# RK3566_SARADC_GPIO.net
KiCad netlist of a schematic drawn in Altium Designer
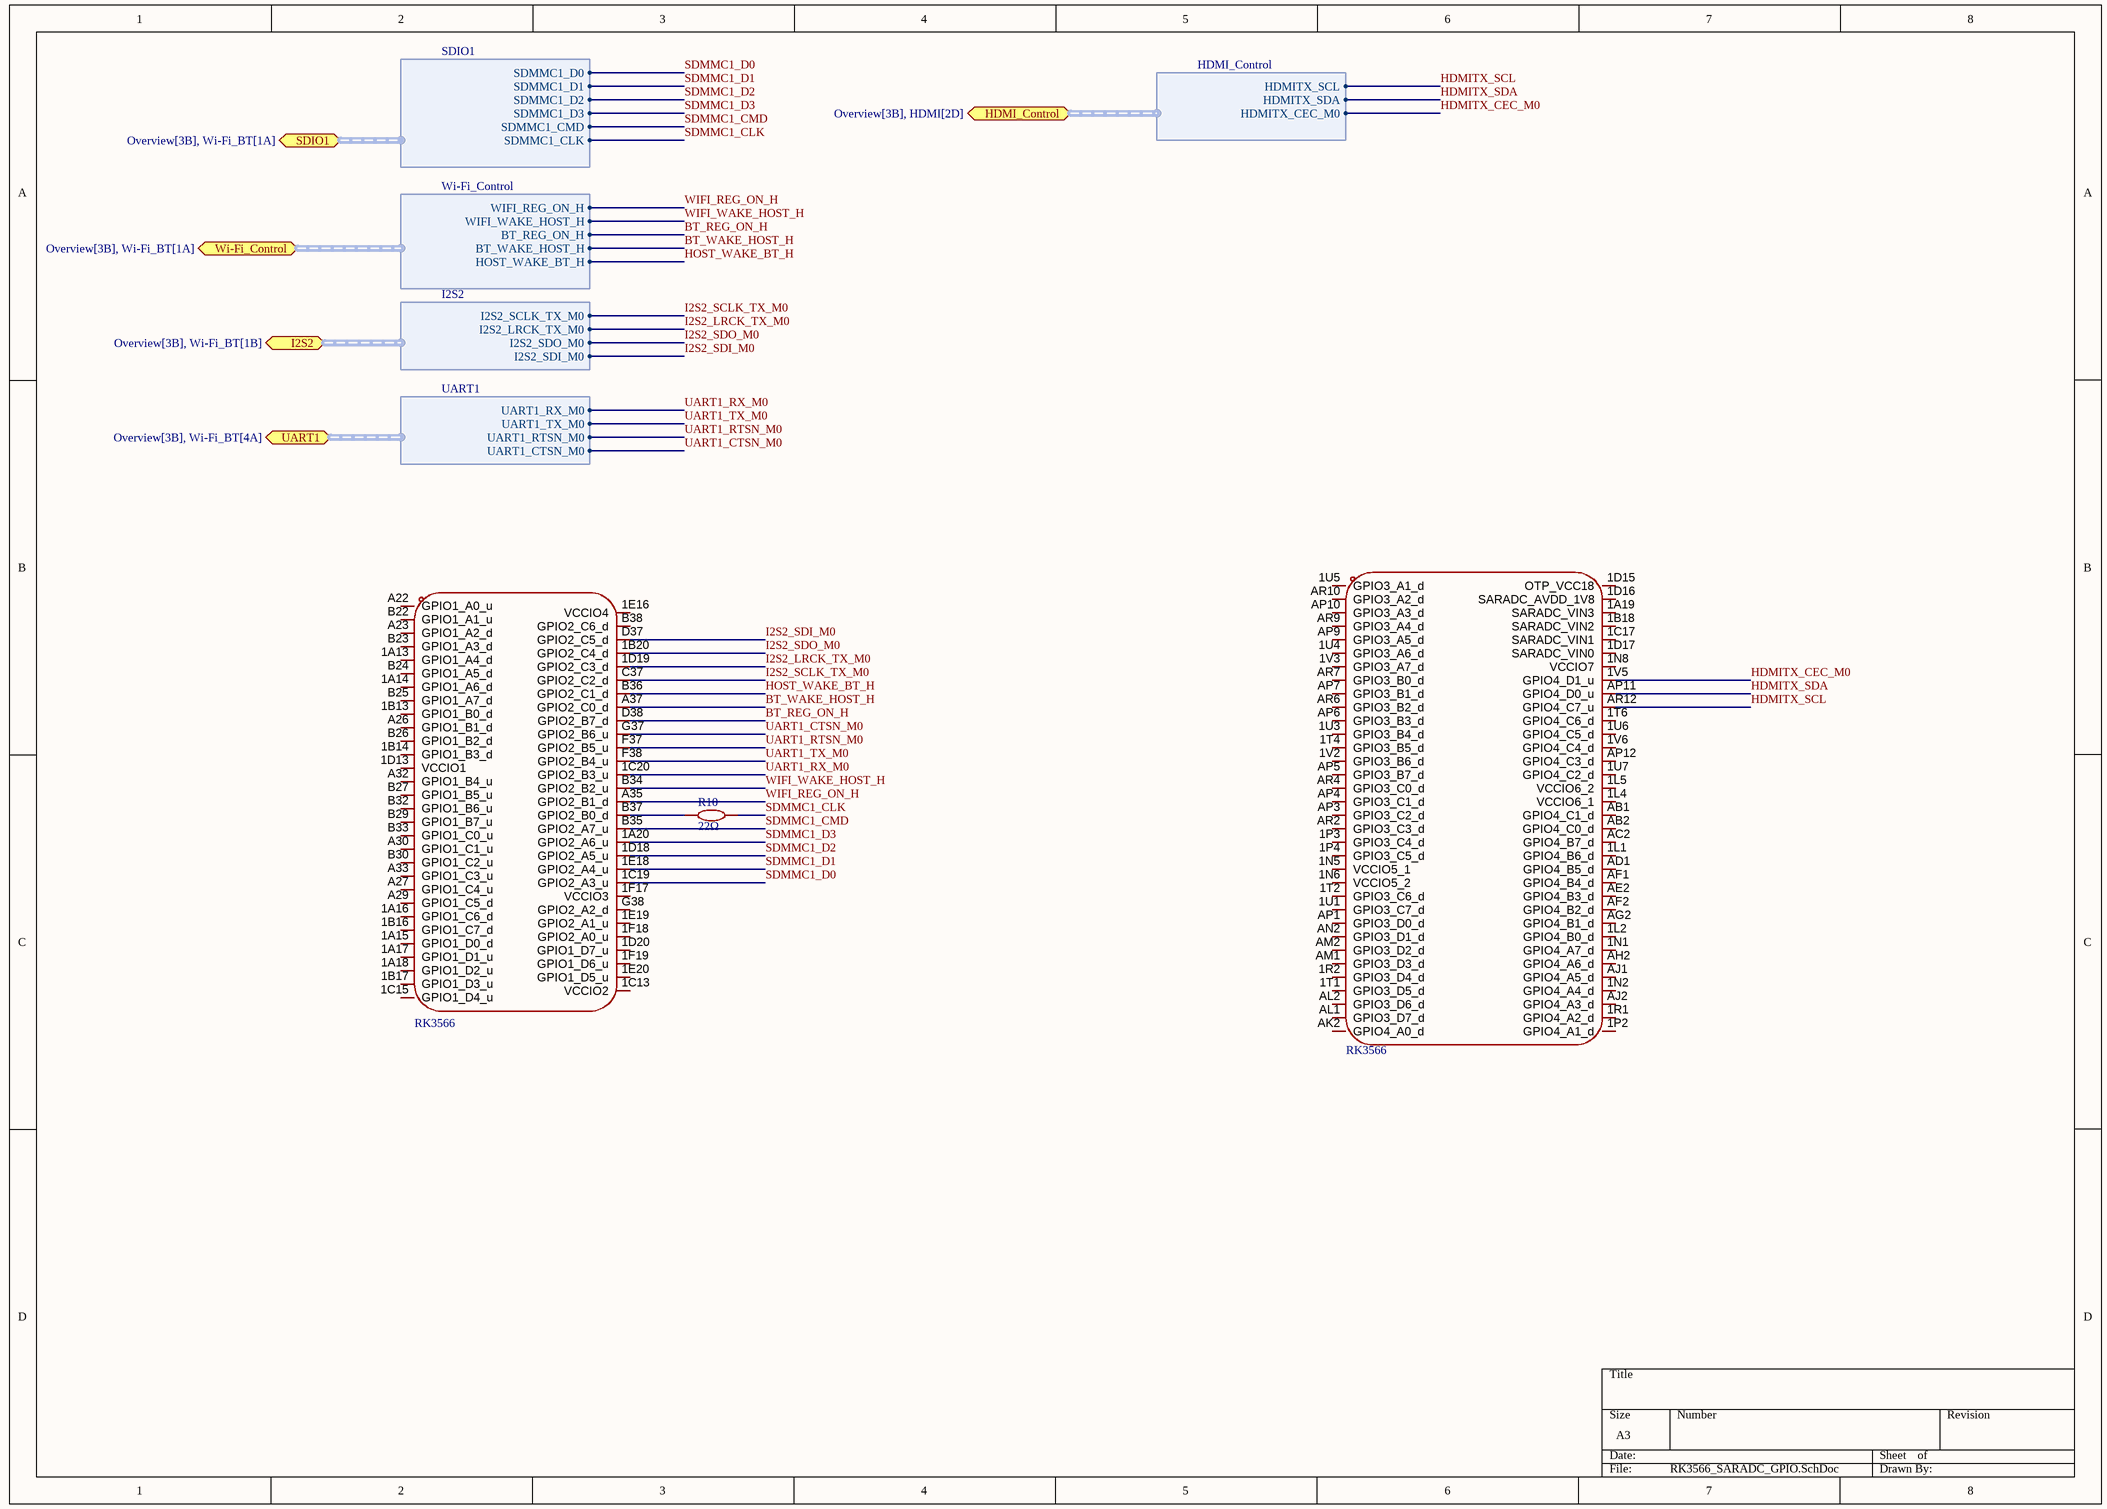
[diagram p0: RK3566_SARADC_GPIO.SchDoc]

(export (version "E")
  (design (tool "Eeschema 10.0.6"))
  (components
    (comp (ref "R10")
      (value "22Ω")
      (footprint "R0402")
      (description "62.5mW 33Ω 50V ±100ppm/℃ Thick Film Resistor ±1% 0402 Chip Resistor - Surface Mount ROHS")
      (libsource (lib "RLC") (part "22Ω"))
    )
    (comp (ref "U1")
      (value "RK3566")
      (footprint "BGA-565_L15.5-W14.4-P0.40_RK3566_1")
      (description "BGA-565(15.5x14.4)")
      (libsource (lib "IC") (part "RK3566"))
    )
  )
  (nets
    (net (code "6") (name "/BT_REG_ON_H") (class "Default")
      (node (ref "U1") (pin "D38") (pinfunction "GPIO2_B7_d_D38") (pintype "passive"))
    )
    (net (code "7") (name "/BT_WAKE_HOST_H") (class "Default")
      (node (ref "U1") (pin "A37") (pinfunction "GPIO2_C0_d_A37") (pintype "passive"))
    )
    (net (code "8") (name "/HDMITX_CEC_M0") (class "Default")
      (node (ref "U1") (pin "1V5") (pinfunction "GPIO4_D1_u_1V5") (pintype "passive"))
    )
    (net (code "9") (name "/HDMITX_SCL") (class "Default")
      (node (ref "U1") (pin "AR12") (pinfunction "GPIO4_C7_u_AR12") (pintype "passive"))
    )
    (net (code "10") (name "/HDMITX_SDA") (class "Default")
      (node (ref "U1") (pin "AP11") (pinfunction "GPIO4_D0_u_AP11") (pintype "passive"))
    )
    (net (code "11") (name "/HOST_WAKE_BT_H") (class "Default")
      (node (ref "U1") (pin "B36") (pinfunction "GPIO2_C1_d_B36") (pintype "passive"))
    )
    (net (code "12") (name "/I2S2_LRCK_TX_M0") (class "Default")
      (node (ref "U1") (pin "1D19") (pinfunction "GPIO2_C3_d_1D19") (pintype "passive"))
    )
    (net (code "13") (name "/I2S2_SCLK_TX_M0") (class "Default")
      (node (ref "U1") (pin "C37") (pinfunction "GPIO2_C2_d_C37") (pintype "passive"))
    )
    (net (code "14") (name "/I2S2_SDI_M0") (class "Default")
      (node (ref "U1") (pin "D37") (pinfunction "GPIO2_C5_d_D37") (pintype "passive"))
    )
    (net (code "15") (name "/I2S2_SDO_M0") (class "Default")
      (node (ref "U1") (pin "1B20") (pinfunction "GPIO2_C4_d_1B20") (pintype "passive"))
    )
    (net (code "16") (name "/SDMMC1_CLK") (class "Default")
      (node (ref "R10") (pin "2") (pinfunction "2_2") (pintype "passive"))
    )
    (net (code "17") (name "/SDMMC1_CMD") (class "Default")
      (node (ref "U1") (pin "B35") (pinfunction "GPIO2_A7_u_B35") (pintype "passive"))
    )
    (net (code "18") (name "/SDMMC1_D0") (class "Default")
      (node (ref "U1") (pin "1C19") (pinfunction "GPIO2_A3_u_1C19") (pintype "passive"))
    )
    (net (code "19") (name "/SDMMC1_D1") (class "Default")
      (node (ref "U1") (pin "1E18") (pinfunction "GPIO2_A4_u_1E18") (pintype "passive"))
    )
    (net (code "20") (name "/SDMMC1_D2") (class "Default")
      (node (ref "U1") (pin "1D18") (pinfunction "GPIO2_A5_u_1D18") (pintype "passive"))
    )
    (net (code "21") (name "/SDMMC1_D3") (class "Default")
      (node (ref "U1") (pin "1A20") (pinfunction "GPIO2_A6_u_1A20") (pintype "passive"))
    )
    (net (code "22") (name "/UART1_CTSN_M0") (class "Default")
      (node (ref "U1") (pin "G37") (pinfunction "GPIO2_B6_u_G37") (pintype "passive"))
    )
    (net (code "23") (name "/UART1_RTSN_M0") (class "Default")
      (node (ref "U1") (pin "F37") (pinfunction "GPIO2_B5_u_F37") (pintype "passive"))
    )
    (net (code "24") (name "/UART1_RX_M0") (class "Default")
      (node (ref "U1") (pin "1C20") (pinfunction "GPIO2_B3_u_1C20") (pintype "passive"))
    )
    (net (code "25") (name "/UART1_TX_M0") (class "Default")
      (node (ref "U1") (pin "F38") (pinfunction "GPIO2_B4_u_F38") (pintype "passive"))
    )
    (net (code "26") (name "/WIFI_REG_ON_H") (class "Default")
      (node (ref "U1") (pin "A35") (pinfunction "GPIO2_B1_d_A35") (pintype "passive"))
    )
    (net (code "27") (name "/WIFI_WAKE_HOST_H") (class "Default")
      (node (ref "U1") (pin "B34") (pinfunction "GPIO2_B2_u_B34") (pintype "passive"))
    )
    (net (code "33") (name "Net-(U1E-GPIO2_B0_d)") (class "Default")
      (node (ref "R10") (pin "1") (pinfunction "1_1") (pintype "passive"))
      (node (ref "U1") (pin "B37") (pinfunction "GPIO2_B0_d_B37") (pintype "passive"))
    )
    (net (code "34") (name "unconnected-(U1E-GPIO1_A0_u-PadA22)") (class "Default")
      (node (ref "U1") (pin "A22") (pinfunction "GPIO1_A0_u_A22") (pintype "passive"))
    )
    (net (code "35") (name "unconnected-(U1E-GPIO1_A1_u-PadB22)") (class "Default")
      (node (ref "U1") (pin "B22") (pinfunction "GPIO1_A1_u_B22") (pintype "passive"))
    )
    (net (code "36") (name "unconnected-(U1E-GPIO1_A2_d-PadA23)") (class "Default")
      (node (ref "U1") (pin "A23") (pinfunction "GPIO1_A2_d_A23") (pintype "passive"))
    )
    (net (code "37") (name "unconnected-(U1E-GPIO1_A3_d-PadB23)") (class "Default")
      (node (ref "U1") (pin "B23") (pinfunction "GPIO1_A3_d_B23") (pintype "passive"))
    )
    (net (code "38") (name "unconnected-(U1E-GPIO1_A4_d-Pad1A13)") (class "Default")
      (node (ref "U1") (pin "1A13") (pinfunction "GPIO1_A4_d_1A13") (pintype "passive"))
    )
    (net (code "39") (name "unconnected-(U1E-GPIO1_A5_d-PadB24)") (class "Default")
      (node (ref "U1") (pin "B24") (pinfunction "GPIO1_A5_d_B24") (pintype "passive"))
    )
    (net (code "40") (name "unconnected-(U1E-GPIO1_A6_d-Pad1A14)") (class "Default")
      (node (ref "U1") (pin "1A14") (pinfunction "GPIO1_A6_d_1A14") (pintype "passive"))
    )
    (net (code "41") (name "unconnected-(U1E-GPIO1_A7_d-PadB25)") (class "Default")
      (node (ref "U1") (pin "B25") (pinfunction "GPIO1_A7_d_B25") (pintype "passive"))
    )
    (net (code "42") (name "unconnected-(U1E-GPIO1_B0_d-Pad1B13)") (class "Default")
      (node (ref "U1") (pin "1B13") (pinfunction "GPIO1_B0_d_1B13") (pintype "passive"))
    )
    (net (code "43") (name "unconnected-(U1E-GPIO1_B1_d-PadA26)") (class "Default")
      (node (ref "U1") (pin "A26") (pinfunction "GPIO1_B1_d_A26") (pintype "passive"))
    )
    (net (code "44") (name "unconnected-(U1E-GPIO1_B2_d-PadB26)") (class "Default")
      (node (ref "U1") (pin "B26") (pinfunction "GPIO1_B2_d_B26") (pintype "passive"))
    )
    (net (code "45") (name "unconnected-(U1E-GPIO1_B3_d-Pad1B14)") (class "Default")
      (node (ref "U1") (pin "1B14") (pinfunction "GPIO1_B3_d_1B14") (pintype "passive"))
    )
    (net (code "46") (name "unconnected-(U1E-GPIO1_B4_u-PadA32)") (class "Default")
      (node (ref "U1") (pin "A32") (pinfunction "GPIO1_B4_u_A32") (pintype "passive"))
    )
    (net (code "47") (name "unconnected-(U1E-GPIO1_B5_u-PadB27)") (class "Default")
      (node (ref "U1") (pin "B27") (pinfunction "GPIO1_B5_u_B27") (pintype "passive"))
    )
    (net (code "48") (name "unconnected-(U1E-GPIO1_B6_u-PadB32)") (class "Default")
      (node (ref "U1") (pin "B32") (pinfunction "GPIO1_B6_u_B32") (pintype "passive"))
    )
    (net (code "49") (name "unconnected-(U1E-GPIO1_B7_u-PadB29)") (class "Default")
      (node (ref "U1") (pin "B29") (pinfunction "GPIO1_B7_u_B29") (pintype "passive"))
    )
    (net (code "50") (name "unconnected-(U1E-GPIO1_C0_u-PadB33)") (class "Default")
      (node (ref "U1") (pin "B33") (pinfunction "GPIO1_C0_u_B33") (pintype "passive"))
    )
    (net (code "51") (name "unconnected-(U1E-GPIO1_C1_u-PadA30)") (class "Default")
      (node (ref "U1") (pin "A30") (pinfunction "GPIO1_C1_u_A30") (pintype "passive"))
    )
    (net (code "52") (name "unconnected-(U1E-GPIO1_C2_u-PadB30)") (class "Default")
      (node (ref "U1") (pin "B30") (pinfunction "GPIO1_C2_u_B30") (pintype "passive"))
    )
    (net (code "53") (name "unconnected-(U1E-GPIO1_C3_u-PadA33)") (class "Default")
      (node (ref "U1") (pin "A33") (pinfunction "GPIO1_C3_u_A33") (pintype "passive"))
    )
    (net (code "54") (name "unconnected-(U1E-GPIO1_C4_u-PadA27)") (class "Default")
      (node (ref "U1") (pin "A27") (pinfunction "GPIO1_C4_u_A27") (pintype "passive"))
    )
    (net (code "55") (name "unconnected-(U1E-GPIO1_C5_d-PadA29)") (class "Default")
      (node (ref "U1") (pin "A29") (pinfunction "GPIO1_C5_d_A29") (pintype "passive"))
    )
    (net (code "56") (name "unconnected-(U1E-GPIO1_C6_d-Pad1A16)") (class "Default")
      (node (ref "U1") (pin "1A16") (pinfunction "GPIO1_C6_d_1A16") (pintype "passive"))
    )
    (net (code "57") (name "unconnected-(U1E-GPIO1_C7_d-Pad1B16)") (class "Default")
      (node (ref "U1") (pin "1B16") (pinfunction "GPIO1_C7_d_1B16") (pintype "passive"))
    )
    (net (code "58") (name "unconnected-(U1E-GPIO1_D0_d-Pad1A15)") (class "Default")
      (node (ref "U1") (pin "1A15") (pinfunction "GPIO1_D0_d_1A15") (pintype "passive"))
    )
    (net (code "59") (name "unconnected-(U1E-GPIO1_D1_u-Pad1A17)") (class "Default")
      (node (ref "U1") (pin "1A17") (pinfunction "GPIO1_D1_u_1A17") (pintype "passive"))
    )
    (net (code "60") (name "unconnected-(U1E-GPIO1_D2_u-Pad1A18)") (class "Default")
      (node (ref "U1") (pin "1A18") (pinfunction "GPIO1_D2_u_1A18") (pintype "passive"))
    )
    (net (code "61") (name "unconnected-(U1E-GPIO1_D3_u-Pad1B17)") (class "Default")
      (node (ref "U1") (pin "1B17") (pinfunction "GPIO1_D3_u_1B17") (pintype "passive"))
    )
    (net (code "62") (name "unconnected-(U1E-GPIO1_D4_u-Pad1C15)") (class "Default")
      (node (ref "U1") (pin "1C15") (pinfunction "GPIO1_D4_u_1C15") (pintype "passive"))
    )
    (net (code "63") (name "unconnected-(U1E-GPIO1_D5_u-Pad1E20)") (class "Default")
      (node (ref "U1") (pin "1E20") (pinfunction "GPIO1_D5_u_1E20") (pintype "passive"))
    )
    (net (code "64") (name "unconnected-(U1E-GPIO1_D6_u-Pad1F19)") (class "Default")
      (node (ref "U1") (pin "1F19") (pinfunction "GPIO1_D6_u_1F19") (pintype "passive"))
    )
    (net (code "65") (name "unconnected-(U1E-GPIO1_D7_u-Pad1D20)") (class "Default")
      (node (ref "U1") (pin "1D20") (pinfunction "GPIO1_D7_u_1D20") (pintype "passive"))
    )
    (net (code "66") (name "unconnected-(U1E-GPIO2_A0_u-Pad1F18)") (class "Default")
      (node (ref "U1") (pin "1F18") (pinfunction "GPIO2_A0_u_1F18") (pintype "passive"))
    )
    (net (code "67") (name "unconnected-(U1E-GPIO2_A1_u-Pad1E19)") (class "Default")
      (node (ref "U1") (pin "1E19") (pinfunction "GPIO2_A1_u_1E19") (pintype "passive"))
    )
    (net (code "68") (name "unconnected-(U1E-GPIO2_A2_d-PadG38)") (class "Default")
      (node (ref "U1") (pin "G38") (pinfunction "GPIO2_A2_d_G38") (pintype "passive"))
    )
    (net (code "69") (name "unconnected-(U1E-GPIO2_C6_d-PadB38)") (class "Default")
      (node (ref "U1") (pin "B38") (pinfunction "GPIO2_C6_d_B38") (pintype "passive"))
    )
    (net (code "70") (name "unconnected-(U1E-VCCIO1-Pad1D13)") (class "Default")
      (node (ref "U1") (pin "1D13") (pinfunction "VCCIO1_1D13") (pintype "passive"))
    )
    (net (code "71") (name "unconnected-(U1E-VCCIO2-Pad1C13)") (class "Default")
      (node (ref "U1") (pin "1C13") (pinfunction "VCCIO2_1C13") (pintype "passive"))
    )
    (net (code "72") (name "unconnected-(U1E-VCCIO3-Pad1F17)") (class "Default")
      (node (ref "U1") (pin "1F17") (pinfunction "VCCIO3_1F17") (pintype "passive"))
    )
    (net (code "73") (name "unconnected-(U1E-VCCIO4-Pad1E16)") (class "Default")
      (node (ref "U1") (pin "1E16") (pinfunction "VCCIO4_1E16") (pintype "passive"))
    )
    (net (code "74") (name "unconnected-(U1F-GPIO3_A1_d-Pad1U5)") (class "Default")
      (node (ref "U1") (pin "1U5") (pinfunction "GPIO3_A1_d_1U5") (pintype "passive"))
    )
    (net (code "75") (name "unconnected-(U1F-GPIO3_A2_d-PadAR10)") (class "Default")
      (node (ref "U1") (pin "AR10") (pinfunction "GPIO3_A2_d_AR10") (pintype "passive"))
    )
    (net (code "76") (name "unconnected-(U1F-GPIO3_A3_d-PadAP10)") (class "Default")
      (node (ref "U1") (pin "AP10") (pinfunction "GPIO3_A3_d_AP10") (pintype "passive"))
    )
    (net (code "77") (name "unconnected-(U1F-GPIO3_A4_d-PadAR9)") (class "Default")
      (node (ref "U1") (pin "AR9") (pinfunction "GPIO3_A4_d_AR9") (pintype "passive"))
    )
    (net (code "78") (name "unconnected-(U1F-GPIO3_A5_d-PadAP9)") (class "Default")
      (node (ref "U1") (pin "AP9") (pinfunction "GPIO3_A5_d_AP9") (pintype "passive"))
    )
    (net (code "79") (name "unconnected-(U1F-GPIO3_A6_d-Pad1U4)") (class "Default")
      (node (ref "U1") (pin "1U4") (pinfunction "GPIO3_A6_d_1U4") (pintype "passive"))
    )
    (net (code "80") (name "unconnected-(U1F-GPIO3_A7_d-Pad1V3)") (class "Default")
      (node (ref "U1") (pin "1V3") (pinfunction "GPIO3_A7_d_1V3") (pintype "passive"))
    )
    (net (code "81") (name "unconnected-(U1F-GPIO3_B0_d-PadAR7)") (class "Default")
      (node (ref "U1") (pin "AR7") (pinfunction "GPIO3_B0_d_AR7") (pintype "passive"))
    )
    (net (code "82") (name "unconnected-(U1F-GPIO3_B1_d-PadAP7)") (class "Default")
      (node (ref "U1") (pin "AP7") (pinfunction "GPIO3_B1_d_AP7") (pintype "passive"))
    )
    (net (code "83") (name "unconnected-(U1F-GPIO3_B2_d-PadAR6)") (class "Default")
      (node (ref "U1") (pin "AR6") (pinfunction "GPIO3_B2_d_AR6") (pintype "passive"))
    )
    (net (code "84") (name "unconnected-(U1F-GPIO3_B3_d-PadAP6)") (class "Default")
      (node (ref "U1") (pin "AP6") (pinfunction "GPIO3_B3_d_AP6") (pintype "passive"))
    )
    (net (code "85") (name "unconnected-(U1F-GPIO3_B4_d-Pad1U3)") (class "Default")
      (node (ref "U1") (pin "1U3") (pinfunction "GPIO3_B4_d_1U3") (pintype "passive"))
    )
    (net (code "86") (name "unconnected-(U1F-GPIO3_B5_d-Pad1T4)") (class "Default")
      (node (ref "U1") (pin "1T4") (pinfunction "GPIO3_B5_d_1T4") (pintype "passive"))
    )
    (net (code "87") (name "unconnected-(U1F-GPIO3_B6_d-Pad1V2)") (class "Default")
      (node (ref "U1") (pin "1V2") (pinfunction "GPIO3_B6_d_1V2") (pintype "passive"))
    )
    (net (code "88") (name "unconnected-(U1F-GPIO3_B7_d-PadAP5)") (class "Default")
      (node (ref "U1") (pin "AP5") (pinfunction "GPIO3_B7_d_AP5") (pintype "passive"))
    )
    (net (code "89") (name "unconnected-(U1F-GPIO3_C0_d-PadAR4)") (class "Default")
      (node (ref "U1") (pin "AR4") (pinfunction "GPIO3_C0_d_AR4") (pintype "passive"))
    )
    (net (code "90") (name "unconnected-(U1F-GPIO3_C1_d-PadAP4)") (class "Default")
      (node (ref "U1") (pin "AP4") (pinfunction "GPIO3_C1_d_AP4") (pintype "passive"))
    )
    (net (code "91") (name "unconnected-(U1F-GPIO3_C2_d-PadAP3)") (class "Default")
      (node (ref "U1") (pin "AP3") (pinfunction "GPIO3_C2_d_AP3") (pintype "passive"))
    )
    (net (code "92") (name "unconnected-(U1F-GPIO3_C3_d-PadAR2)") (class "Default")
      (node (ref "U1") (pin "AR2") (pinfunction "GPIO3_C3_d_AR2") (pintype "passive"))
    )
    (net (code "93") (name "unconnected-(U1F-GPIO3_C4_d-Pad1P3)") (class "Default")
      (node (ref "U1") (pin "1P3") (pinfunction "GPIO3_C4_d_1P3") (pintype "passive"))
    )
    (net (code "94") (name "unconnected-(U1F-GPIO3_C5_d-Pad1P4)") (class "Default")
      (node (ref "U1") (pin "1P4") (pinfunction "GPIO3_C5_d_1P4") (pintype "passive"))
    )
    (net (code "95") (name "unconnected-(U1F-GPIO3_C6_d-Pad1T2)") (class "Default")
      (node (ref "U1") (pin "1T2") (pinfunction "GPIO3_C6_d_1T2") (pintype "passive"))
    )
    (net (code "96") (name "unconnected-(U1F-GPIO3_C7_d-Pad1U1)") (class "Default")
      (node (ref "U1") (pin "1U1") (pinfunction "GPIO3_C7_d_1U1") (pintype "passive"))
    )
    (net (code "97") (name "unconnected-(U1F-GPIO3_D0_d-PadAP1)") (class "Default")
      (node (ref "U1") (pin "AP1") (pinfunction "GPIO3_D0_d_AP1") (pintype "passive"))
    )
    (net (code "98") (name "unconnected-(U1F-GPIO3_D1_d-PadAN2)") (class "Default")
      (node (ref "U1") (pin "AN2") (pinfunction "GPIO3_D1_d_AN2") (pintype "passive"))
    )
    (net (code "99") (name "unconnected-(U1F-GPIO3_D2_d-PadAM2)") (class "Default")
      (node (ref "U1") (pin "AM2") (pinfunction "GPIO3_D2_d_AM2") (pintype "passive"))
    )
    (net (code "100") (name "unconnected-(U1F-GPIO3_D3_d-PadAM1)") (class "Default")
      (node (ref "U1") (pin "AM1") (pinfunction "GPIO3_D3_d_AM1") (pintype "passive"))
    )
    (net (code "101") (name "unconnected-(U1F-GPIO3_D4_d-Pad1R2)") (class "Default")
      (node (ref "U1") (pin "1R2") (pinfunction "GPIO3_D4_d_1R2") (pintype "passive"))
    )
    (net (code "102") (name "unconnected-(U1F-GPIO3_D5_d-Pad1T1)") (class "Default")
      (node (ref "U1") (pin "1T1") (pinfunction "GPIO3_D5_d_1T1") (pintype "passive"))
    )
    (net (code "103") (name "unconnected-(U1F-GPIO3_D6_d-PadAL2)") (class "Default")
      (node (ref "U1") (pin "AL2") (pinfunction "GPIO3_D6_d_AL2") (pintype "passive"))
    )
    (net (code "104") (name "unconnected-(U1F-GPIO3_D7_d-PadAL1)") (class "Default")
      (node (ref "U1") (pin "AL1") (pinfunction "GPIO3_D7_d_AL1") (pintype "passive"))
    )
    (net (code "105") (name "unconnected-(U1F-GPIO4_A0_d-PadAK2)") (class "Default")
      (node (ref "U1") (pin "AK2") (pinfunction "GPIO4_A0_d_AK2") (pintype "passive"))
    )
    (net (code "106") (name "unconnected-(U1F-GPIO4_A1_d-Pad1P2)") (class "Default")
      (node (ref "U1") (pin "1P2") (pinfunction "GPIO4_A1_d_1P2") (pintype "passive"))
    )
    (net (code "107") (name "unconnected-(U1F-GPIO4_A2_d-Pad1R1)") (class "Default")
      (node (ref "U1") (pin "1R1") (pinfunction "GPIO4_A2_d_1R1") (pintype "passive"))
    )
    (net (code "108") (name "unconnected-(U1F-GPIO4_A3_d-PadAJ2)") (class "Default")
      (node (ref "U1") (pin "AJ2") (pinfunction "GPIO4_A3_d_AJ2") (pintype "passive"))
    )
    (net (code "109") (name "unconnected-(U1F-GPIO4_A4_d-Pad1N2)") (class "Default")
      (node (ref "U1") (pin "1N2") (pinfunction "GPIO4_A4_d_1N2") (pintype "passive"))
    )
    (net (code "110") (name "unconnected-(U1F-GPIO4_A5_d-PadAJ1)") (class "Default")
      (node (ref "U1") (pin "AJ1") (pinfunction "GPIO4_A5_d_AJ1") (pintype "passive"))
    )
    (net (code "111") (name "unconnected-(U1F-GPIO4_A6_d-PadAH2)") (class "Default")
      (node (ref "U1") (pin "AH2") (pinfunction "GPIO4_A6_d_AH2") (pintype "passive"))
    )
    (net (code "112") (name "unconnected-(U1F-GPIO4_A7_d-Pad1N1)") (class "Default")
      (node (ref "U1") (pin "1N1") (pinfunction "GPIO4_A7_d_1N1") (pintype "passive"))
    )
    (net (code "113") (name "unconnected-(U1F-GPIO4_B0_d-Pad1L2)") (class "Default")
      (node (ref "U1") (pin "1L2") (pinfunction "GPIO4_B0_d_1L2") (pintype "passive"))
    )
    (net (code "114") (name "unconnected-(U1F-GPIO4_B1_d-PadAG2)") (class "Default")
      (node (ref "U1") (pin "AG2") (pinfunction "GPIO4_B1_d_AG2") (pintype "passive"))
    )
    (net (code "115") (name "unconnected-(U1F-GPIO4_B2_d-PadAF2)") (class "Default")
      (node (ref "U1") (pin "AF2") (pinfunction "GPIO4_B2_d_AF2") (pintype "passive"))
    )
    (net (code "116") (name "unconnected-(U1F-GPIO4_B3_d-PadAE2)") (class "Default")
      (node (ref "U1") (pin "AE2") (pinfunction "GPIO4_B3_d_AE2") (pintype "passive"))
    )
    (net (code "117") (name "unconnected-(U1F-GPIO4_B4_d-PadAF1)") (class "Default")
      (node (ref "U1") (pin "AF1") (pinfunction "GPIO4_B4_d_AF1") (pintype "passive"))
    )
    (net (code "118") (name "unconnected-(U1F-GPIO4_B5_d-PadAD1)") (class "Default")
      (node (ref "U1") (pin "AD1") (pinfunction "GPIO4_B5_d_AD1") (pintype "passive"))
    )
    (net (code "119") (name "unconnected-(U1F-GPIO4_B6_d-Pad1L1)") (class "Default")
      (node (ref "U1") (pin "1L1") (pinfunction "GPIO4_B6_d_1L1") (pintype "passive"))
    )
    (net (code "120") (name "unconnected-(U1F-GPIO4_B7_d-PadAC2)") (class "Default")
      (node (ref "U1") (pin "AC2") (pinfunction "GPIO4_B7_d_AC2") (pintype "passive"))
    )
    (net (code "121") (name "unconnected-(U1F-GPIO4_C0_d-PadAB2)") (class "Default")
      (node (ref "U1") (pin "AB2") (pinfunction "GPIO4_C0_d_AB2") (pintype "passive"))
    )
    (net (code "122") (name "unconnected-(U1F-GPIO4_C1_d-PadAB1)") (class "Default")
      (node (ref "U1") (pin "AB1") (pinfunction "GPIO4_C1_d_AB1") (pintype "passive"))
    )
    (net (code "123") (name "unconnected-(U1F-GPIO4_C2_d-Pad1U7)") (class "Default")
      (node (ref "U1") (pin "1U7") (pinfunction "GPIO4_C2_d_1U7") (pintype "passive"))
    )
    (net (code "124") (name "unconnected-(U1F-GPIO4_C3_d-PadAP12)") (class "Default")
      (node (ref "U1") (pin "AP12") (pinfunction "GPIO4_C3_d_AP12") (pintype "passive"))
    )
    (net (code "125") (name "unconnected-(U1F-GPIO4_C4_d-Pad1V6)") (class "Default")
      (node (ref "U1") (pin "1V6") (pinfunction "GPIO4_C4_d_1V6") (pintype "passive"))
    )
    (net (code "126") (name "unconnected-(U1F-GPIO4_C5_d-Pad1U6)") (class "Default")
      (node (ref "U1") (pin "1U6") (pinfunction "GPIO4_C5_d_1U6") (pintype "passive"))
    )
    (net (code "127") (name "unconnected-(U1F-GPIO4_C6_d-Pad1T6)") (class "Default")
      (node (ref "U1") (pin "1T6") (pinfunction "GPIO4_C6_d_1T6") (pintype "passive"))
    )
    (net (code "128") (name "unconnected-(U1F-OTP_VCC18-Pad1D15)") (class "Default")
      (node (ref "U1") (pin "1D15") (pinfunction "OTP_VCC18_1D15") (pintype "passive"))
    )
    (net (code "129") (name "unconnected-(U1F-SARADC_AVDD_1V8-Pad1D16)") (class "Default")
      (node (ref "U1") (pin "1D16") (pinfunction "SARADC_AVDD_1V8_1D16") (pintype "passive"))
    )
    (net (code "130") (name "unconnected-(U1F-SARADC_VIN0-Pad1D17)") (class "Default")
      (node (ref "U1") (pin "1D17") (pinfunction "SARADC_VIN0_1D17") (pintype "passive"))
    )
    (net (code "131") (name "unconnected-(U1F-SARADC_VIN1-Pad1C17)") (class "Default")
      (node (ref "U1") (pin "1C17") (pinfunction "SARADC_VIN1_1C17") (pintype "passive"))
    )
    (net (code "132") (name "unconnected-(U1F-SARADC_VIN2-Pad1B18)") (class "Default")
      (node (ref "U1") (pin "1B18") (pinfunction "SARADC_VIN2_1B18") (pintype "passive"))
    )
    (net (code "133") (name "unconnected-(U1F-SARADC_VIN3-Pad1A19)") (class "Default")
      (node (ref "U1") (pin "1A19") (pinfunction "SARADC_VIN3_1A19") (pintype "passive"))
    )
    (net (code "134") (name "unconnected-(U1F-VCCIO5_1-Pad1N5)") (class "Default")
      (node (ref "U1") (pin "1N5") (pinfunction "VCCIO5_1_1N5") (pintype "passive"))
    )
    (net (code "135") (name "unconnected-(U1F-VCCIO5_2-Pad1N6)") (class "Default")
      (node (ref "U1") (pin "1N6") (pinfunction "VCCIO5_2_1N6") (pintype "passive"))
    )
    (net (code "136") (name "unconnected-(U1F-VCCIO6_1-Pad1L4)") (class "Default")
      (node (ref "U1") (pin "1L4") (pinfunction "VCCIO6_1_1L4") (pintype "passive"))
    )
    (net (code "137") (name "unconnected-(U1F-VCCIO6_2-Pad1L5)") (class "Default")
      (node (ref "U1") (pin "1L5") (pinfunction "VCCIO6_2_1L5") (pintype "passive"))
    )
    (net (code "138") (name "unconnected-(U1F-VCCIO7-Pad1N8)") (class "Default")
      (node (ref "U1") (pin "1N8") (pinfunction "VCCIO7_1N8") (pintype "passive"))
    )
  )
)
